# kicker.net
KiCad netlist of a schematic drawn in EAGLE
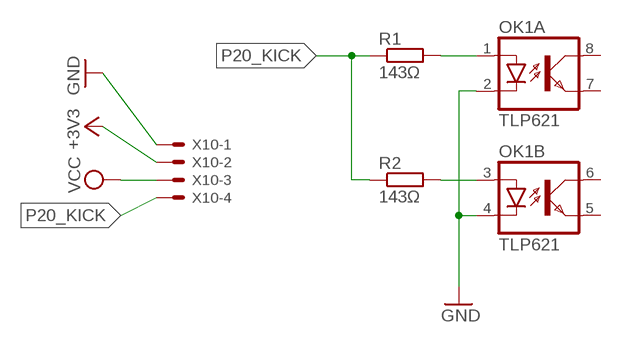
[diagram p0: schematic, sheet 1]

(export (version "E")
  (design (tool "Eeschema 10.0.6"))
  (components
    (comp (ref "OK1")
      (value "TLP621")
      (footprint "eagle-import:DIL08")
      (libsource (lib "eagle-import") (part "PC827"))
    )
    (comp (ref "R1")
      (value "143Ω")
      (footprint "eagle-import:0207_10")
      (libsource (lib "eagle-import") (part "R-EU_0207/10"))
    )
    (comp (ref "R2")
      (value "143Ω")
      (footprint "eagle-import:0207_10")
      (libsource (lib "eagle-import") (part "R-EU_0207/10"))
    )
    (comp (ref "X10")
      (value "Kicker")
      (footprint "eagle-import:JST-XH-04-PACKAGE-ROUND-PAD")
      (libsource (lib "eagle-import") (part "JST-XH-04-PIN-ROUND-PAD"))
    )
  )
  (nets
    (net (code "1") (name "+3V3") (class "Default")
      (node (ref "X10") (pin "2") (pinfunction "S_2") (pintype "passive"))
    )
    (net (code "2") (name "GND") (class "Default")
      (node (ref "OK1") (pin "2") (pinfunction "C_2") (pintype "passive"))
      (node (ref "OK1") (pin "4") (pinfunction "C_4") (pintype "passive"))
      (node (ref "X10") (pin "1") (pinfunction "S_1") (pintype "passive"))
    )
    (net (code "3") (name "Net-(OK1A-A)") (class "Default")
      (node (ref "OK1") (pin "1") (pinfunction "A_1") (pintype "passive"))
      (node (ref "R1") (pin "2") (pinfunction "2_2") (pintype "passive"))
    )
    (net (code "4") (name "Net-(OK1B-A)") (class "Default")
      (node (ref "OK1") (pin "3") (pinfunction "A_3") (pintype "passive"))
      (node (ref "R2") (pin "2") (pinfunction "2_2") (pintype "passive"))
    )
    (net (code "5") (name "P20_KICK") (class "Default")
      (node (ref "R1") (pin "1") (pinfunction "1_1") (pintype "passive"))
      (node (ref "R2") (pin "1") (pinfunction "1_1") (pintype "passive"))
      (node (ref "X10") (pin "4") (pinfunction "S_4") (pintype "passive"))
    )
    (net (code "6") (name "VCC") (class "Default")
      (node (ref "X10") (pin "3") (pinfunction "S_3") (pintype "passive"))
    )
    (net (code "7") (name "unconnected-(OK1A-COL-Pad8)") (class "Default")
      (node (ref "OK1") (pin "8") (pinfunction "COL_8") (pintype "passive"))
    )
    (net (code "8") (name "unconnected-(OK1A-EMIT-Pad7)") (class "Default")
      (node (ref "OK1") (pin "7") (pinfunction "EMIT_7") (pintype "passive"))
    )
    (net (code "9") (name "unconnected-(OK1B-COL-Pad6)") (class "Default")
      (node (ref "OK1") (pin "6") (pinfunction "COL_6") (pintype "passive"))
    )
    (net (code "10") (name "unconnected-(OK1B-EMIT-Pad5)") (class "Default")
      (node (ref "OK1") (pin "5") (pinfunction "EMIT_5") (pintype "passive"))
    )
  )
)
